# LightingUPS_v4.net
KiCad netlist of a schematic drawn in EAGLE
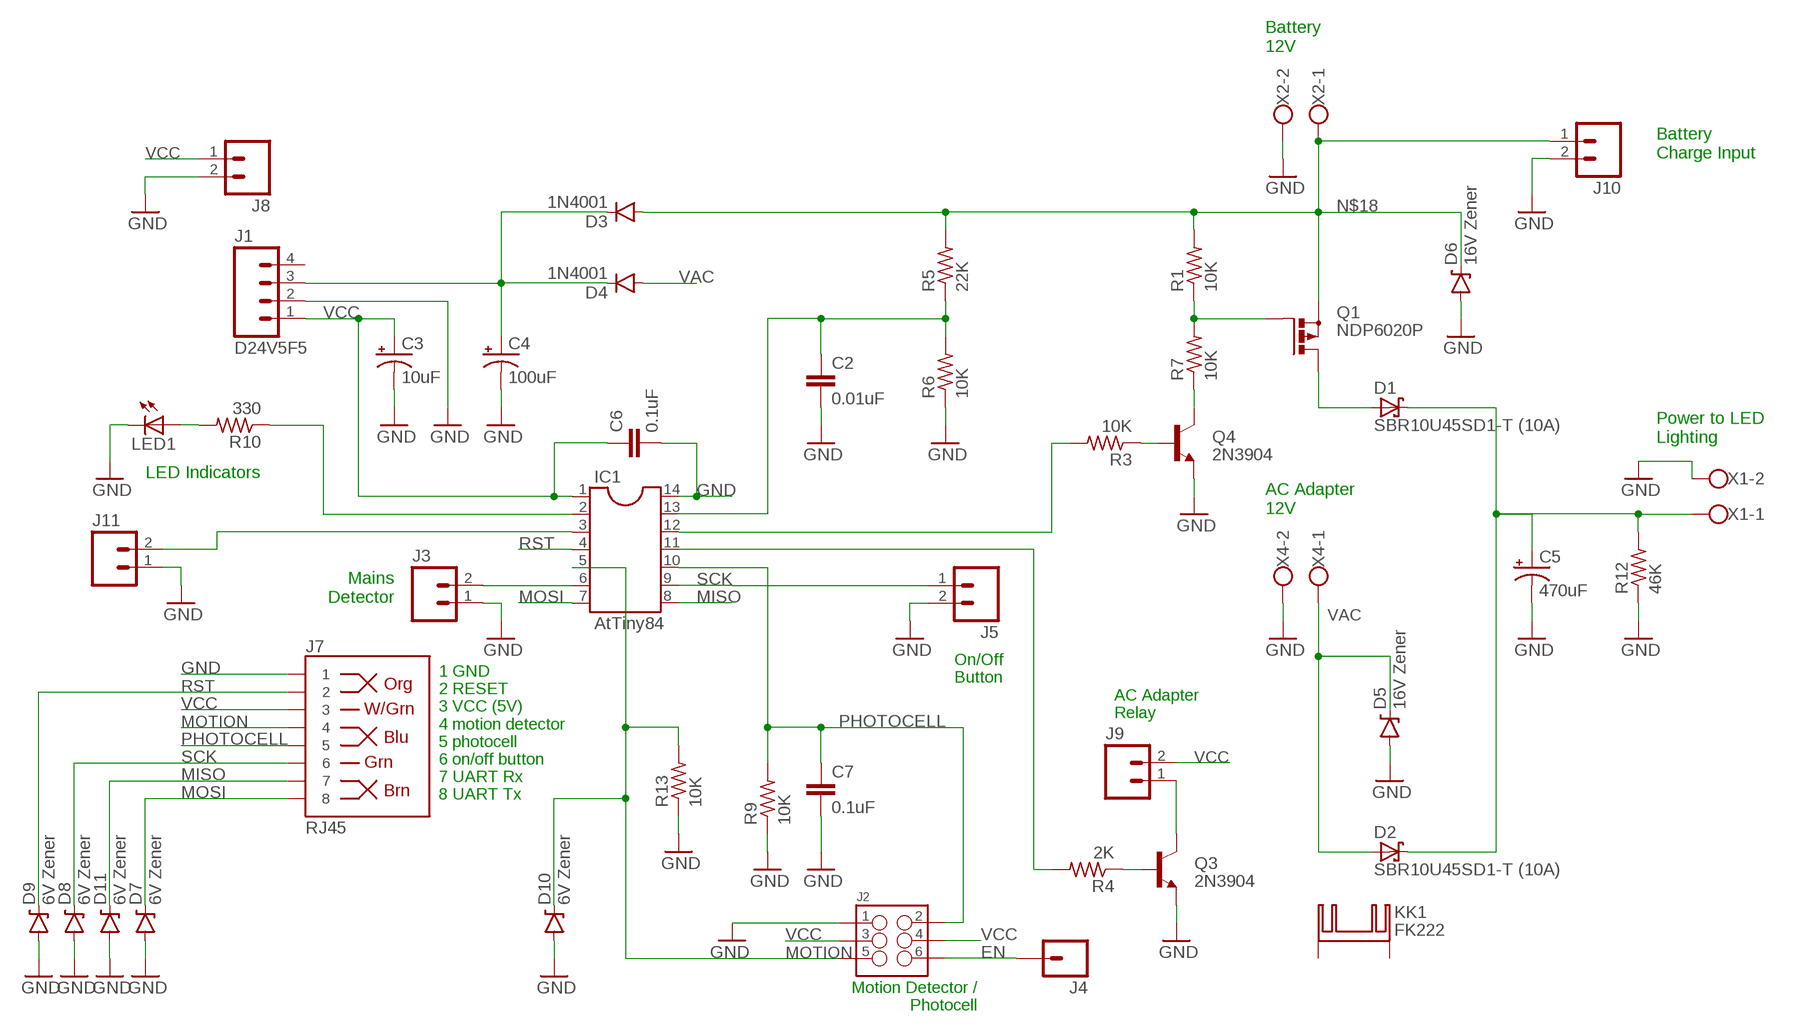
[diagram p0: schematic, sheet 1]

(export (version "E")
  (design (tool "Eeschema 10.0.6"))
  (components
    (comp (ref "C2")
      (value "0.01uF")
      (footprint "eagle-import:CAP-PTH-5MM")
      (libsource (lib "eagle-import") (part "SparkFun-Passives_CAPPTH1"))
    )
    (comp (ref "C3")
      (value "10uF")
      (footprint "eagle-import:CPOL-RADIAL-100UF-25V")
      (libsource (lib "eagle-import") (part "CAP_POLPTH1"))
    )
    (comp (ref "C4")
      (value "100uF")
      (footprint "eagle-import:CPOL-RADIAL-100UF-25V")
      (libsource (lib "eagle-import") (part "CAP_POLPTH1"))
    )
    (comp (ref "C5")
      (value "470uF")
      (footprint "eagle-import:CPOL-RADIAL-1000UF-25V")
      (libsource (lib "eagle-import") (part "CAP_POLPTH4"))
    )
    (comp (ref "C6")
      (value "0.1uF")
      (footprint "eagle-import:CAP-PTH-SMALL")
      (libsource (lib "eagle-import") (part "CAPPTH"))
    )
    (comp (ref "C7")
      (value "0.1uF")
      (footprint "eagle-import:CAP-PTH-SMALL")
      (libsource (lib "eagle-import") (part "CAPPTH"))
    )
    (comp (ref "D1")
      (value "SBR10U45SD1-T (10A)")
      (footprint "eagle-import:DO201T15")
      (libsource (lib "eagle-import") (part "SCHOTTKY-DIODEDO201T15"))
    )
    (comp (ref "D2")
      (value "SBR10U45SD1-T (10A)")
      (footprint "eagle-import:DO201T15")
      (libsource (lib "eagle-import") (part "SCHOTTKY-DIODEDO201T15"))
    )
    (comp (ref "D3")
      (value "1N4001")
      (footprint "eagle-import:DIODE-1N4001")
      (libsource (lib "eagle-import") (part "DIODEPTH"))
    )
    (comp (ref "D4")
      (value "1N4001")
      (footprint "eagle-import:DIODE-1N4001")
      (libsource (lib "eagle-import") (part "DIODEPTH"))
    )
    (comp (ref "D5")
      (value "16V Zener")
      (footprint "eagle-import:DIODE-ZENER")
      (libsource (lib "eagle-import") (part "DIODE-ZENERPTH"))
    )
    (comp (ref "D6")
      (value "16V Zener")
      (footprint "eagle-import:DIODE-ZENER")
      (libsource (lib "eagle-import") (part "DIODE-ZENERPTH"))
    )
    (comp (ref "D7")
      (value "6V Zener")
      (footprint "eagle-import:DIODE-ZENER")
      (libsource (lib "eagle-import") (part "DIODE-ZENERPTH"))
    )
    (comp (ref "D8")
      (value "6V Zener")
      (footprint "eagle-import:DIODE-ZENER")
      (libsource (lib "eagle-import") (part "DIODE-ZENERPTH"))
    )
    (comp (ref "D9")
      (value "6V Zener")
      (footprint "eagle-import:DIODE-ZENER")
      (libsource (lib "eagle-import") (part "DIODE-ZENERPTH"))
    )
    (comp (ref "D10")
      (value "6V Zener")
      (footprint "eagle-import:DIODE-ZENER")
      (libsource (lib "eagle-import") (part "DIODE-ZENERPTH"))
    )
    (comp (ref "D11")
      (value "6V Zener")
      (footprint "eagle-import:DIODE-ZENER")
      (libsource (lib "eagle-import") (part "DIODE-ZENERPTH"))
    )
    (comp (ref "IC1")
      (value "AtTiny84")
      (footprint "eagle-import:DIL14")
      (libsource (lib "eagle-import") (part "DIL14"))
    )
    (comp (ref "J1")
      (value "D24V5F5")
      (footprint "eagle-import:1X04")
      (libsource (lib "eagle-import") (part "M04PTH"))
    )
    (comp (ref "J2")
      (value "M03X2SHROUD")
      (footprint "eagle-import:2X3-SHROUDED")
      (libsource (lib "eagle-import") (part "M03X2SHROUD"))
    )
    (comp (ref "J3")
      (value "M02PTH")
      (footprint "eagle-import:1X02")
      (libsource (lib "eagle-import") (part "M02PTH"))
    )
    (comp (ref "J4")
      (value "M01PTH")
      (footprint "eagle-import:1X01")
      (libsource (lib "eagle-import") (part "M01PTH"))
    )
    (comp (ref "J5")
      (value "M02PTH")
      (footprint "eagle-import:1X02")
      (libsource (lib "eagle-import") (part "M02PTH"))
    )
    (comp (ref "J7")
      (value "RJ45")
      (footprint "eagle-import:RJ45-8")
      (libsource (lib "eagle-import") (part "RJ45-8PTH"))
    )
    (comp (ref "J8")
      (value "M02PTH")
      (footprint "eagle-import:1X02")
      (libsource (lib "eagle-import") (part "M02PTH"))
    )
    (comp (ref "J9")
      (value "M02PTH")
      (footprint "eagle-import:1X02")
      (libsource (lib "eagle-import") (part "M02PTH"))
    )
    (comp (ref "J10")
      (value "M02PTH")
      (footprint "eagle-import:1X02")
      (libsource (lib "eagle-import") (part "M02PTH"))
    )
    (comp (ref "J11")
      (value "M02PTH")
      (footprint "eagle-import:1X02")
      (libsource (lib "eagle-import") (part "M02PTH"))
    )
    (comp (ref "KK1")
      (value "FK222")
      (footprint "eagle-import:FK222")
      (libsource (lib "eagle-import") (part "FK222"))
    )
    (comp (ref "LED1")
      (value "LED5MM")
      (footprint "eagle-import:LED5MM")
      (libsource (lib "eagle-import") (part "LED5MM"))
    )
    (comp (ref "Q1")
      (value "NDP6020P")
      (footprint "eagle-import:TO220BV")
      (libsource (lib "eagle-import") (part "PMOSFET_PTO220BV"))
    )
    (comp (ref "Q3")
      (value "2N3904")
      (footprint "eagle-import:TO-92-AMMO")
      (libsource (lib "eagle-import") (part "TRANSISTOR_NPNTO-92-AMMO"))
    )
    (comp (ref "Q4")
      (value "2N3904")
      (footprint "eagle-import:TO-92-AMMO")
      (libsource (lib "eagle-import") (part "TRANSISTOR_NPNTO-92-AMMO"))
    )
    (comp (ref "R1")
      (value "10K")
      (footprint "eagle-import:0204_5")
      (libsource (lib "eagle-import") (part "R-US_0204/5"))
    )
    (comp (ref "R3")
      (value "10K")
      (footprint "eagle-import:0204_5")
      (libsource (lib "eagle-import") (part "R-US_0204/5"))
    )
    (comp (ref "R4")
      (value "2K")
      (footprint "eagle-import:0204_5")
      (libsource (lib "eagle-import") (part "R-US_0204/5"))
    )
    (comp (ref "R5")
      (value "22K")
      (footprint "eagle-import:0204_5")
      (libsource (lib "eagle-import") (part "R-US_0204/5"))
    )
    (comp (ref "R6")
      (value "10K")
      (footprint "eagle-import:0204_5")
      (libsource (lib "eagle-import") (part "R-US_0204/5"))
    )
    (comp (ref "R7")
      (value "10K")
      (footprint "eagle-import:0204_5")
      (libsource (lib "eagle-import") (part "R-US_0204/5"))
    )
    (comp (ref "R9")
      (value "10K")
      (footprint "eagle-import:0204_5")
      (libsource (lib "eagle-import") (part "R-US_0204/5"))
    )
    (comp (ref "R10")
      (value "330")
      (footprint "eagle-import:0204_5")
      (libsource (lib "eagle-import") (part "R-US_0204/5"))
    )
    (comp (ref "R12")
      (value "46K")
      (footprint "eagle-import:0204_5")
      (libsource (lib "eagle-import") (part "R-US_0204/5"))
    )
    (comp (ref "R13")
      (value "10K")
      (footprint "eagle-import:0204_5")
      (libsource (lib "eagle-import") (part "R-US_0204/5"))
    )
    (comp (ref "X1")
      (value "W237-102")
      (footprint "eagle-import:W237-102")
      (fields (field (name "MPN") "237-102"))
      (libsource (lib "eagle-import") (part "W237-102"))
    )
    (comp (ref "X2")
      (value "W237-102")
      (footprint "eagle-import:W237-102")
      (fields (field (name "MPN") "237-102"))
      (libsource (lib "eagle-import") (part "W237-102"))
    )
    (comp (ref "X4")
      (value "W237-102")
      (footprint "eagle-import:W237-102")
      (fields (field (name "MPN") "237-102"))
      (libsource (lib "eagle-import") (part "W237-102"))
    )
  )
  (nets
    (net (code "1") (name "/EN") (class "Default")
      (node (ref "J2") (pin "6") (pinfunction "6_6") (pintype "bidirectional"))
      (node (ref "J4") (pin "1") (pinfunction "1_1") (pintype "passive"))
    )
    (net (code "2") (name "/MISO") (class "Default")
      (node (ref "D11") (pin "P$1") (pinfunction "C_P$1") (pintype "passive"))
      (node (ref "IC1") (pin "8") (pinfunction "8_8") (pintype "passive"))
      (node (ref "J7") (pin "7") (pinfunction "7_7") (pintype "bidirectional"))
    )
    (net (code "3") (name "/MOSI") (class "Default")
      (node (ref "D7") (pin "P$1") (pinfunction "C_P$1") (pintype "passive"))
      (node (ref "IC1") (pin "7") (pinfunction "7_7") (pintype "passive"))
      (node (ref "J7") (pin "8") (pinfunction "8_8") (pintype "bidirectional"))
    )
    (net (code "4") (name "/MOTION") (class "Default")
      (node (ref "D10") (pin "P$1") (pinfunction "C_P$1") (pintype "passive"))
      (node (ref "IC1") (pin "5") (pinfunction "5_5") (pintype "passive"))
      (node (ref "J2") (pin "5") (pinfunction "5_5") (pintype "bidirectional"))
      (node (ref "J7") (pin "4") (pinfunction "4_4") (pintype "bidirectional"))
      (node (ref "R13") (pin "2") (pinfunction "2_2") (pintype "passive"))
    )
    (net (code "5") (name "/N$18") (class "Default")
      (node (ref "D3") (pin "A") (pinfunction "A_A") (pintype "passive"))
      (node (ref "D6") (pin "P$1") (pinfunction "C_P$1") (pintype "passive"))
      (node (ref "J10") (pin "1") (pinfunction "1_1") (pintype "passive"))
      (node (ref "Q1") (pin "S") (pinfunction "S_S") (pintype "passive"))
      (node (ref "R1") (pin "2") (pinfunction "2_2") (pintype "passive"))
      (node (ref "R5") (pin "2") (pinfunction "2_2") (pintype "passive"))
      (node (ref "X2") (pin "1") (pinfunction "KL_1") (pintype "passive"))
    )
    (net (code "6") (name "/PHOTOCELL") (class "Default")
      (node (ref "C7") (pin "1") (pinfunction "1_1") (pintype "passive"))
      (node (ref "IC1") (pin "10") (pinfunction "10_10") (pintype "passive"))
      (node (ref "J2") (pin "2") (pinfunction "2_2") (pintype "bidirectional"))
      (node (ref "J7") (pin "5") (pinfunction "5_5") (pintype "bidirectional"))
      (node (ref "R9") (pin "2") (pinfunction "2_2") (pintype "passive"))
    )
    (net (code "7") (name "/RST") (class "Default")
      (node (ref "D9") (pin "P$1") (pinfunction "C_P$1") (pintype "passive"))
      (node (ref "IC1") (pin "4") (pinfunction "4_4") (pintype "passive"))
      (node (ref "J7") (pin "2") (pinfunction "2_2") (pintype "bidirectional"))
    )
    (net (code "8") (name "/SCK") (class "Default")
      (node (ref "D8") (pin "P$1") (pinfunction "C_P$1") (pintype "passive"))
      (node (ref "IC1") (pin "9") (pinfunction "9_9") (pintype "passive"))
      (node (ref "J5") (pin "1") (pinfunction "1_1") (pintype "passive"))
      (node (ref "J7") (pin "6") (pinfunction "6_6") (pintype "bidirectional"))
    )
    (net (code "9") (name "/VAC") (class "Default")
      (node (ref "D2") (pin "A") (pinfunction "A_A") (pintype "passive"))
      (node (ref "D4") (pin "A") (pinfunction "A_A") (pintype "passive"))
      (node (ref "D5") (pin "P$1") (pinfunction "C_P$1") (pintype "passive"))
      (node (ref "X4") (pin "1") (pinfunction "KL_1") (pintype "passive"))
    )
    (net (code "10") (name "/VCC") (class "Default")
      (node (ref "C3") (pin "1") (pinfunction "+_1") (pintype "passive"))
      (node (ref "C6") (pin "1") (pinfunction "1_1") (pintype "passive"))
      (node (ref "IC1") (pin "1") (pinfunction "1_1") (pintype "passive"))
      (node (ref "J1") (pin "1") (pinfunction "1_1") (pintype "passive"))
      (node (ref "J2") (pin "3") (pinfunction "3_3") (pintype "bidirectional"))
      (node (ref "J2") (pin "4") (pinfunction "4_4") (pintype "bidirectional"))
      (node (ref "J7") (pin "3") (pinfunction "3_3") (pintype "bidirectional"))
      (node (ref "J8") (pin "1") (pinfunction "1_1") (pintype "passive"))
      (node (ref "J9") (pin "2") (pinfunction "2_2") (pintype "passive"))
    )
    (net (code "11") (name "GND") (class "Default")
      (node (ref "C2") (pin "2") (pinfunction "2_2") (pintype "passive"))
      (node (ref "C3") (pin "2") (pinfunction "-_2") (pintype "passive"))
      (node (ref "C4") (pin "2") (pinfunction "-_2") (pintype "passive"))
      (node (ref "C5") (pin "-") (pinfunction "-_-") (pintype "passive"))
      (node (ref "C6") (pin "2") (pinfunction "2_2") (pintype "passive"))
      (node (ref "C7") (pin "2") (pinfunction "2_2") (pintype "passive"))
      (node (ref "D10") (pin "P$2") (pinfunction "A_P$2") (pintype "passive"))
      (node (ref "D11") (pin "P$2") (pinfunction "A_P$2") (pintype "passive"))
      (node (ref "D5") (pin "P$2") (pinfunction "A_P$2") (pintype "passive"))
      (node (ref "D6") (pin "P$2") (pinfunction "A_P$2") (pintype "passive"))
      (node (ref "D7") (pin "P$2") (pinfunction "A_P$2") (pintype "passive"))
      (node (ref "D8") (pin "P$2") (pinfunction "A_P$2") (pintype "passive"))
      (node (ref "D9") (pin "P$2") (pinfunction "A_P$2") (pintype "passive"))
      (node (ref "IC1") (pin "14") (pinfunction "14_14") (pintype "passive"))
      (node (ref "J1") (pin "2") (pinfunction "2_2") (pintype "passive"))
      (node (ref "J10") (pin "2") (pinfunction "2_2") (pintype "passive"))
      (node (ref "J11") (pin "1") (pinfunction "1_1") (pintype "passive"))
      (node (ref "J2") (pin "1") (pinfunction "1_1") (pintype "bidirectional"))
      (node (ref "J3") (pin "1") (pinfunction "1_1") (pintype "passive"))
      (node (ref "J5") (pin "2") (pinfunction "2_2") (pintype "passive"))
      (node (ref "J7") (pin "1") (pinfunction "1_1") (pintype "bidirectional"))
      (node (ref "J8") (pin "2") (pinfunction "2_2") (pintype "passive"))
      (node (ref "LED1") (pin "K") (pinfunction "C_K") (pintype "passive"))
      (node (ref "Q3") (pin "1") (pinfunction "E_1") (pintype "passive"))
      (node (ref "Q4") (pin "1") (pinfunction "E_1") (pintype "passive"))
      (node (ref "R12") (pin "1") (pinfunction "1_1") (pintype "passive"))
      (node (ref "R13") (pin "1") (pinfunction "1_1") (pintype "passive"))
      (node (ref "R6") (pin "1") (pinfunction "1_1") (pintype "passive"))
      (node (ref "R9") (pin "1") (pinfunction "1_1") (pintype "passive"))
      (node (ref "X1") (pin "2") (pinfunction "KL_2") (pintype "passive"))
      (node (ref "X2") (pin "2") (pinfunction "KL_2") (pintype "passive"))
      (node (ref "X4") (pin "2") (pinfunction "KL_2") (pintype "passive"))
    )
    (net (code "12") (name "Net-(C2-Pad1)") (class "Default")
      (node (ref "C2") (pin "1") (pinfunction "1_1") (pintype "passive"))
      (node (ref "IC1") (pin "13") (pinfunction "13_13") (pintype "passive"))
      (node (ref "R5") (pin "1") (pinfunction "1_1") (pintype "passive"))
      (node (ref "R6") (pin "2") (pinfunction "2_2") (pintype "passive"))
    )
    (net (code "13") (name "Net-(C4-+)") (class "Default")
      (node (ref "C4") (pin "1") (pinfunction "+_1") (pintype "passive"))
      (node (ref "D3") (pin "C") (pinfunction "C_C") (pintype "passive"))
      (node (ref "D4") (pin "C") (pinfunction "C_C") (pintype "passive"))
      (node (ref "J1") (pin "3") (pinfunction "3_3") (pintype "passive"))
    )
    (net (code "14") (name "Net-(D1-PadA)") (class "Default")
      (node (ref "D1") (pin "A") (pinfunction "A_A") (pintype "passive"))
      (node (ref "Q1") (pin "D") (pinfunction "D_D") (pintype "passive"))
    )
    (net (code "15") (name "Net-(IC1-Pad2)") (class "Default")
      (node (ref "IC1") (pin "2") (pinfunction "2_2") (pintype "passive"))
      (node (ref "R10") (pin "1") (pinfunction "1_1") (pintype "passive"))
    )
    (net (code "16") (name "Net-(IC1-Pad3)") (class "Default")
      (node (ref "IC1") (pin "3") (pinfunction "3_3") (pintype "passive"))
      (node (ref "J11") (pin "2") (pinfunction "2_2") (pintype "passive"))
    )
    (net (code "17") (name "Net-(IC1-Pad6)") (class "Default")
      (node (ref "IC1") (pin "6") (pinfunction "6_6") (pintype "passive"))
      (node (ref "J3") (pin "2") (pinfunction "2_2") (pintype "passive"))
    )
    (net (code "18") (name "Net-(IC1-Pad11)") (class "Default")
      (node (ref "IC1") (pin "11") (pinfunction "11_11") (pintype "passive"))
      (node (ref "R4") (pin "2") (pinfunction "2_2") (pintype "passive"))
    )
    (net (code "19") (name "Net-(IC1-Pad12)") (class "Default")
      (node (ref "IC1") (pin "12") (pinfunction "12_12") (pintype "passive"))
      (node (ref "R3") (pin "2") (pinfunction "2_2") (pintype "passive"))
    )
    (net (code "20") (name "Net-(LED1-PadA)") (class "Default")
      (node (ref "LED1") (pin "A") (pinfunction "A_A") (pintype "passive"))
      (node (ref "R10") (pin "2") (pinfunction "2_2") (pintype "passive"))
    )
    (net (code "21") (name "Net-(Q1-PadG)") (class "Default")
      (node (ref "Q1") (pin "G") (pinfunction "G_G") (pintype "passive"))
      (node (ref "R1") (pin "1") (pinfunction "1_1") (pintype "passive"))
      (node (ref "R7") (pin "2") (pinfunction "2_2") (pintype "passive"))
    )
    (net (code "22") (name "Net-(Q3-B)") (class "Default")
      (node (ref "Q3") (pin "2") (pinfunction "B_2") (pintype "passive"))
      (node (ref "R4") (pin "1") (pinfunction "1_1") (pintype "passive"))
    )
    (net (code "23") (name "Net-(Q3-C)") (class "Default")
      (node (ref "J9") (pin "1") (pinfunction "1_1") (pintype "passive"))
      (node (ref "Q3") (pin "3") (pinfunction "C_3") (pintype "passive"))
    )
    (net (code "24") (name "Net-(Q4-B)") (class "Default")
      (node (ref "Q4") (pin "2") (pinfunction "B_2") (pintype "passive"))
      (node (ref "R3") (pin "1") (pinfunction "1_1") (pintype "passive"))
    )
    (net (code "25") (name "Net-(Q4-C)") (class "Default")
      (node (ref "Q4") (pin "3") (pinfunction "C_3") (pintype "passive"))
      (node (ref "R7") (pin "1") (pinfunction "1_1") (pintype "passive"))
    )
    (net (code "26") (name "Net-(X1A-KL)") (class "Default")
      (node (ref "C5") (pin "+") (pinfunction "+_+") (pintype "passive"))
      (node (ref "D1") (pin "C") (pinfunction "C_C") (pintype "passive"))
      (node (ref "D2") (pin "C") (pinfunction "C_C") (pintype "passive"))
      (node (ref "R12") (pin "2") (pinfunction "2_2") (pintype "passive"))
      (node (ref "X1") (pin "1") (pinfunction "KL_1") (pintype "passive"))
    )
    (net (code "27") (name "unconnected-(J1-Pad4)") (class "Default")
      (node (ref "J1") (pin "4") (pinfunction "4_4") (pintype "passive"))
    )
    (net (code "28") (name "unconnected-(KK1-K-PadA2,8)") (class "Default")
      (node (ref "KK1") (pin "A2,8") (pinfunction "K_A2,8") (pintype "passive"))
    )
    (net (code "29") (name "unconnected-(KK1-K-PadB2,8)") (class "Default")
      (node (ref "KK1") (pin "B2,8") (pinfunction "K_B2,8") (pintype "passive"))
    )
  )
)
